# SCH_Kumar-Semester-2-Capstone_2025-04-02.net
KiCad netlist of a schematic drawn in EasyEDA
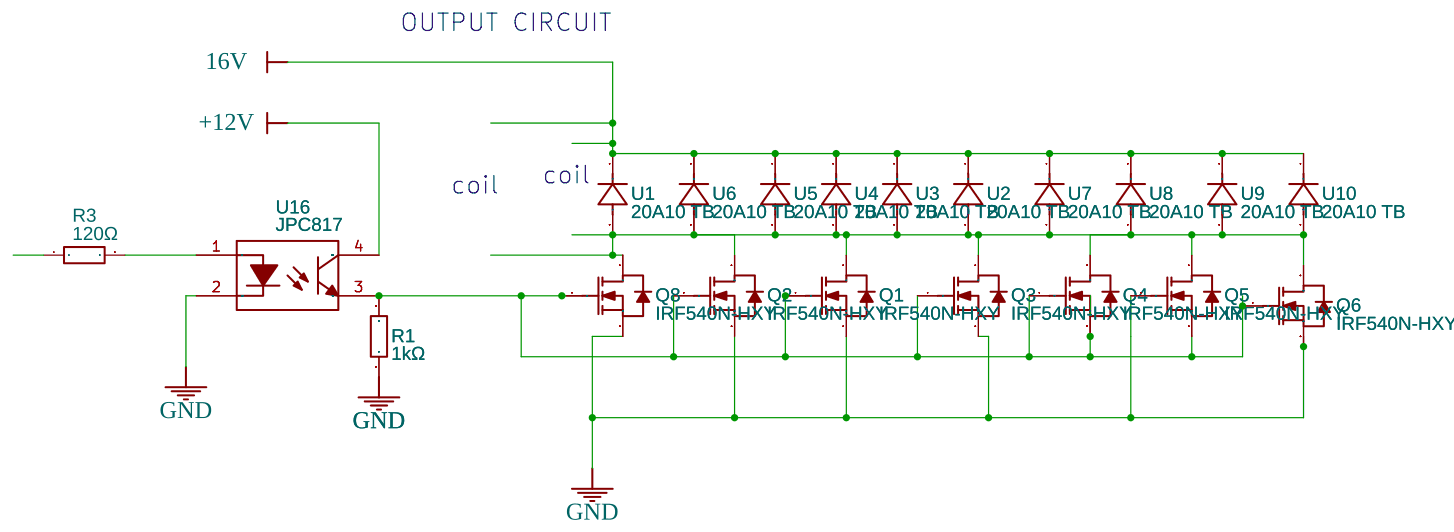
[diagram p0: schematic sheet]

(export (version "E")
  (design (tool "Eeschema 10.0.6"))
  (components
    (comp (ref "Q1")
      (value "IRF540N-HXY")
      (fields (field (name "Manufacturer") "HXY MOSFET(华轩阳电子)"))
      (libsource (lib "") (part "IRF540N-HXY"))
    )
    (comp (ref "Q2")
      (value "IRF540N-HXY")
      (fields (field (name "Manufacturer") "HXY MOSFET(华轩阳电子)"))
      (libsource (lib "") (part "IRF540N-HXY"))
    )
    (comp (ref "Q3")
      (value "IRF540N-HXY")
      (fields (field (name "Manufacturer") "HXY MOSFET(华轩阳电子)"))
      (libsource (lib "") (part "IRF540N-HXY"))
    )
    (comp (ref "Q4")
      (value "IRF540N-HXY")
      (fields (field (name "Manufacturer") "HXY MOSFET(华轩阳电子)"))
      (libsource (lib "") (part "IRF540N-HXY"))
    )
    (comp (ref "Q5")
      (value "IRF540N-HXY")
      (fields (field (name "Manufacturer") "HXY MOSFET(华轩阳电子)"))
      (libsource (lib "") (part "IRF540N-HXY"))
    )
    (comp (ref "Q6")
      (value "IRF540N-HXY")
      (fields (field (name "Manufacturer") "HXY MOSFET(华轩阳电子)"))
      (libsource (lib "") (part "IRF540N-HXY"))
    )
    (comp (ref "Q8")
      (value "IRF540N-HXY")
      (fields (field (name "Manufacturer") "HXY MOSFET(华轩阳电子)"))
      (libsource (lib "") (part "IRF540N-HXY"))
    )
    (comp (ref "R1")
      (value "1kΩ")
      (fields (field (name "Manufacturer Part") "0402 ±5% 1K") (field (name "Manufacturer") "VO(翔胜)"))
      (libsource (lib "") (part "0402 ±5% 1K"))
    )
    (comp (ref "R3")
      (value "120Ω")
      (fields (field (name "Manufacturer Part") "TA205PA120RJ") (field (name "Manufacturer") "Ohmite"))
      (libsource (lib "") (part "TA205PA120RJ"))
    )
    (comp (ref "U1")
      (value "20A10 TB")
      (fields (field (name "Manufacturer") "YFW(佑风微)"))
      (libsource (lib "") (part "20A10 TB"))
    )
    (comp (ref "U2")
      (value "20A10 TB")
      (fields (field (name "Manufacturer") "YFW(佑风微)"))
      (libsource (lib "") (part "20A10 TB"))
    )
    (comp (ref "U3")
      (value "20A10 TB")
      (fields (field (name "Manufacturer") "YFW(佑风微)"))
      (libsource (lib "") (part "20A10 TB"))
    )
    (comp (ref "U4")
      (value "20A10 TB")
      (fields (field (name "Manufacturer") "YFW(佑风微)"))
      (libsource (lib "") (part "20A10 TB"))
    )
    (comp (ref "U5")
      (value "20A10 TB")
      (fields (field (name "Manufacturer") "YFW(佑风微)"))
      (libsource (lib "") (part "20A10 TB"))
    )
    (comp (ref "U6")
      (value "20A10 TB")
      (fields (field (name "Manufacturer") "YFW(佑风微)"))
      (libsource (lib "") (part "20A10 TB"))
    )
    (comp (ref "U7")
      (value "20A10 TB")
      (fields (field (name "Manufacturer") "YFW(佑风微)"))
      (libsource (lib "") (part "20A10 TB"))
    )
    (comp (ref "U8")
      (value "20A10 TB")
      (fields (field (name "Manufacturer") "YFW(佑风微)"))
      (libsource (lib "") (part "20A10 TB"))
    )
    (comp (ref "U9")
      (value "20A10 TB")
      (fields (field (name "Manufacturer") "YFW(佑风微)"))
      (libsource (lib "") (part "20A10 TB"))
    )
    (comp (ref "U10")
      (value "20A10 TB")
      (fields (field (name "Manufacturer") "YFW(佑风微)"))
      (libsource (lib "") (part "20A10 TB"))
    )
    (comp (ref "U16")
      (value "JPC817")
      (fields (field (name "Manufacturer") "JUXING(钜兴)"))
      (libsource (lib "") (part "JPC817"))
    )
  )
  (nets
    (net (code "1") (name "+12V") (class "Default")
      (node (ref "U16") (pin "4") (pinfunction "Collector_4") (pintype "unspecified"))
    )
    (net (code "2") (name "16V") (class "Default")
      (node (ref "U1") (pin "1") (pinfunction "K_1") (pintype "unspecified"))
      (node (ref "U10") (pin "1") (pinfunction "K_1") (pintype "unspecified"))
      (node (ref "U2") (pin "1") (pinfunction "K_1") (pintype "unspecified"))
      (node (ref "U3") (pin "1") (pinfunction "K_1") (pintype "unspecified"))
      (node (ref "U4") (pin "1") (pinfunction "K_1") (pintype "unspecified"))
      (node (ref "U5") (pin "1") (pinfunction "K_1") (pintype "unspecified"))
      (node (ref "U6") (pin "1") (pinfunction "K_1") (pintype "unspecified"))
      (node (ref "U7") (pin "1") (pinfunction "K_1") (pintype "unspecified"))
      (node (ref "U8") (pin "1") (pinfunction "K_1") (pintype "unspecified"))
      (node (ref "U9") (pin "1") (pinfunction "K_1") (pintype "unspecified"))
    )
    (net (code "3") (name "GND") (class "Default")
      (node (ref "Q1") (pin "3") (pinfunction "S_3") (pintype "unspecified"))
      (node (ref "Q2") (pin "3") (pinfunction "S_3") (pintype "unspecified"))
      (node (ref "Q3") (pin "3") (pinfunction "S_3") (pintype "unspecified"))
      (node (ref "Q5") (pin "1") (pinfunction "G_1") (pintype "unspecified"))
      (node (ref "Q6") (pin "3") (pinfunction "S_3") (pintype "unspecified"))
      (node (ref "Q8") (pin "3") (pinfunction "S_3") (pintype "unspecified"))
      (node (ref "R1") (pin "1") (pinfunction "1_1") (pintype "unspecified"))
      (node (ref "U16") (pin "2") (pinfunction "Cathode_2") (pintype "unspecified"))
    )
    (net (code "4") (name "Net-(Q1-D)") (class "Default")
      (node (ref "Q1") (pin "2") (pinfunction "D_2") (pintype "unspecified"))
      (node (ref "Q2") (pin "2") (pinfunction "D_2") (pintype "unspecified"))
      (node (ref "Q3") (pin "2") (pinfunction "D_2") (pintype "unspecified"))
      (node (ref "Q4") (pin "2") (pinfunction "D_2") (pintype "unspecified"))
      (node (ref "Q5") (pin "2") (pinfunction "D_2") (pintype "unspecified"))
      (node (ref "Q6") (pin "2") (pinfunction "D_2") (pintype "unspecified"))
      (node (ref "Q8") (pin "2") (pinfunction "D_2") (pintype "unspecified"))
      (node (ref "U1") (pin "2") (pinfunction "A_2") (pintype "unspecified"))
      (node (ref "U10") (pin "2") (pinfunction "A_2") (pintype "unspecified"))
      (node (ref "U2") (pin "2") (pinfunction "A_2") (pintype "unspecified"))
      (node (ref "U3") (pin "2") (pinfunction "A_2") (pintype "unspecified"))
      (node (ref "U4") (pin "2") (pinfunction "A_2") (pintype "unspecified"))
      (node (ref "U5") (pin "2") (pinfunction "A_2") (pintype "unspecified"))
      (node (ref "U6") (pin "2") (pinfunction "A_2") (pintype "unspecified"))
      (node (ref "U7") (pin "2") (pinfunction "A_2") (pintype "unspecified"))
      (node (ref "U8") (pin "2") (pinfunction "A_2") (pintype "unspecified"))
      (node (ref "U9") (pin "2") (pinfunction "A_2") (pintype "unspecified"))
    )
    (net (code "5") (name "Net-(Q1-G)") (class "Default")
      (node (ref "Q1") (pin "1") (pinfunction "G_1") (pintype "unspecified"))
      (node (ref "Q2") (pin "1") (pinfunction "G_1") (pintype "unspecified"))
      (node (ref "Q3") (pin "1") (pinfunction "G_1") (pintype "unspecified"))
      (node (ref "Q4") (pin "1") (pinfunction "G_1") (pintype "unspecified"))
      (node (ref "Q4") (pin "3") (pinfunction "S_3") (pintype "unspecified"))
      (node (ref "Q5") (pin "3") (pinfunction "S_3") (pintype "unspecified"))
      (node (ref "Q6") (pin "1") (pinfunction "G_1") (pintype "unspecified"))
      (node (ref "Q8") (pin "1") (pinfunction "G_1") (pintype "unspecified"))
      (node (ref "R1") (pin "2") (pinfunction "2_2") (pintype "unspecified"))
      (node (ref "U16") (pin "3") (pinfunction "Emitter_3") (pintype "unspecified"))
    )
    (net (code "6") (name "Net-(U16-Anode)") (class "Default")
      (node (ref "R3") (pin "2") (pinfunction "2_2") (pintype "unspecified"))
      (node (ref "U16") (pin "1") (pinfunction "Anode_1") (pintype "unspecified"))
    )
    (net (code "7") (name "unconnected-(R3-Pad1)") (class "Default")
      (node (ref "R3") (pin "1") (pinfunction "1_1") (pintype "unspecified"))
    )
  )
)
